# ai_breakout_rn52.net
KiCad netlist of a schematic drawn in EAGLE
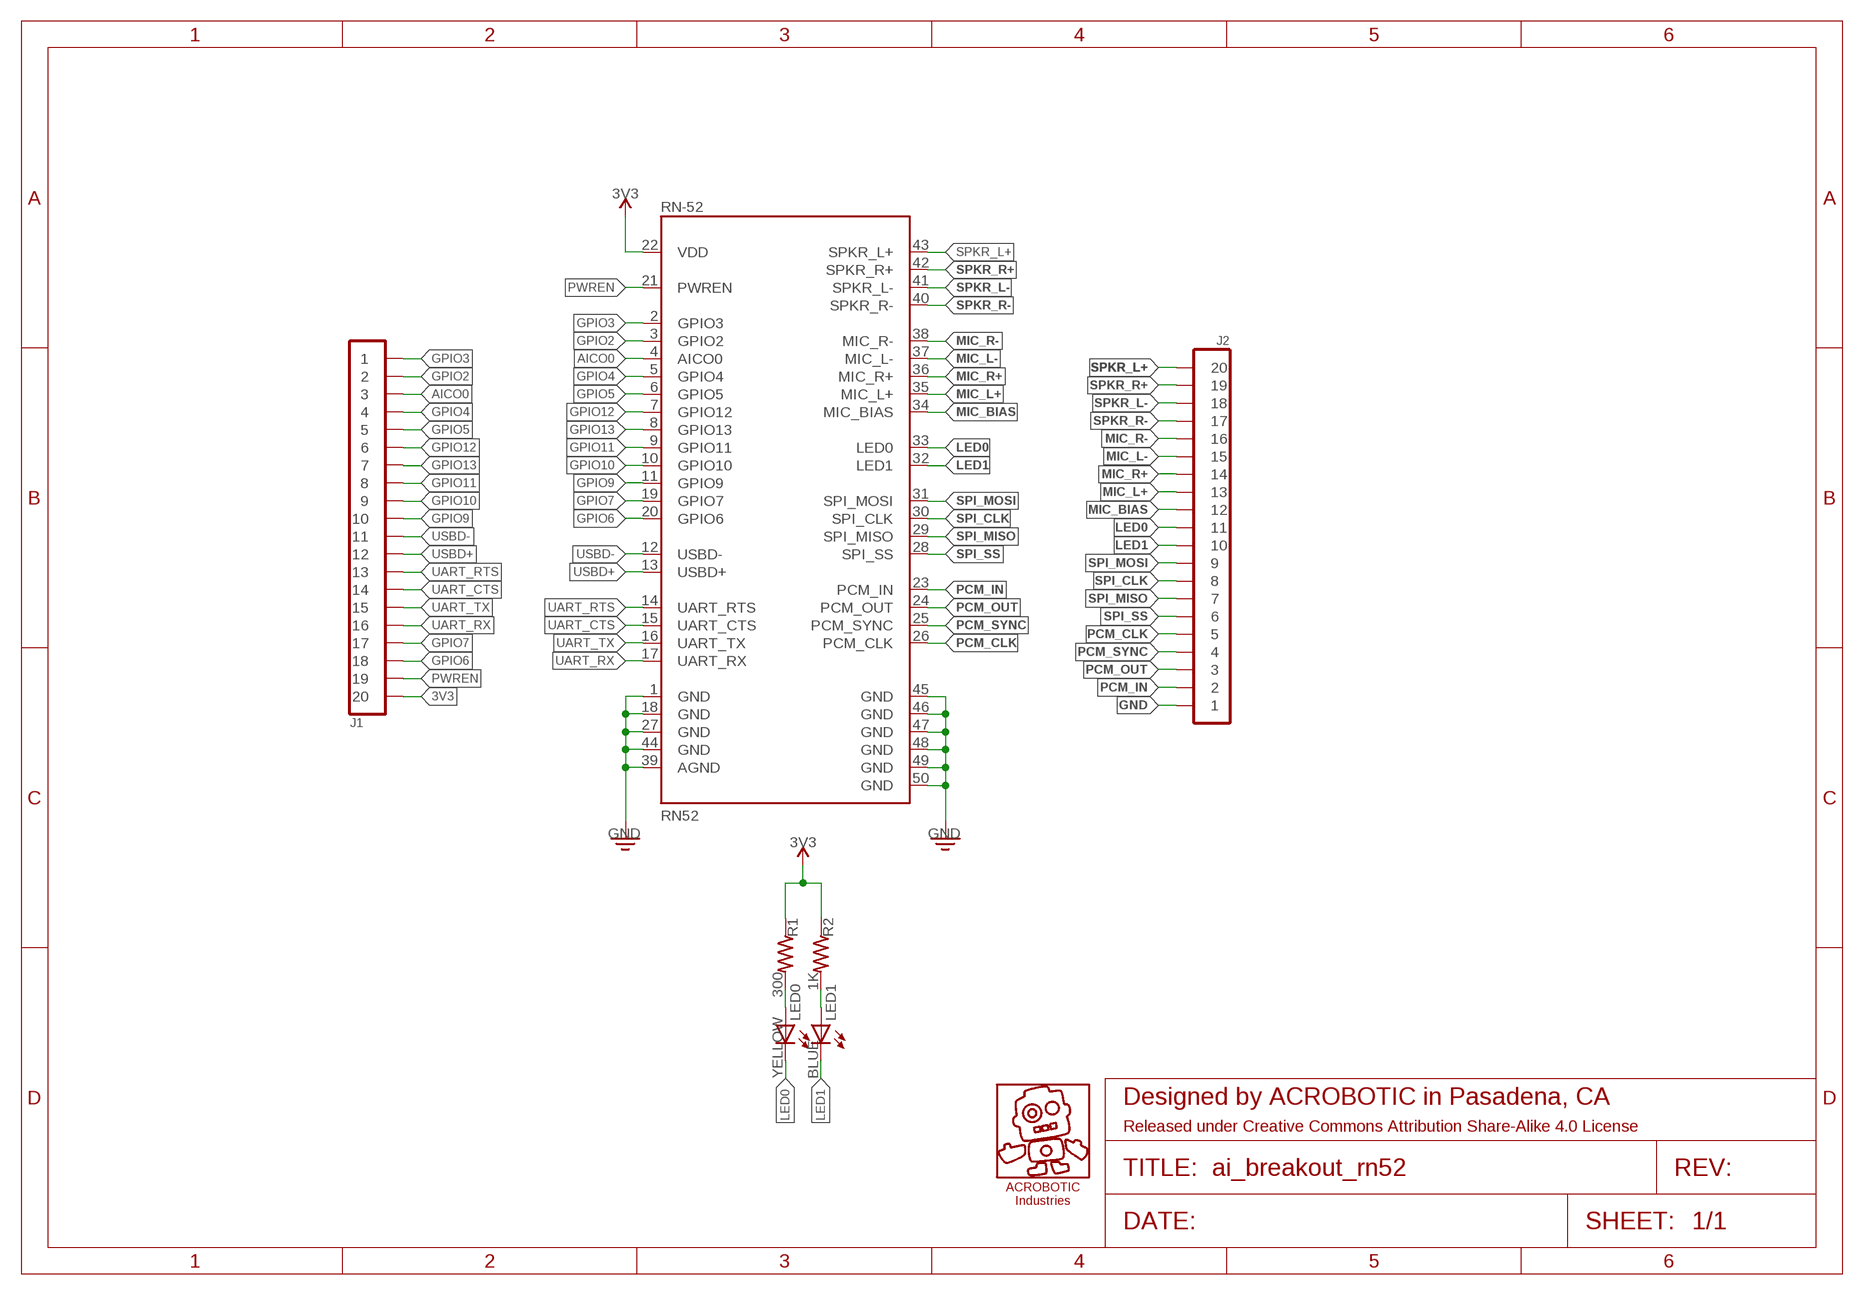
[diagram p0: schematic, sheet 1]

(export (version "E")
  (design (tool "Eeschema 10.0.6"))
  (components
    (comp (ref "FRAME1")
      (value "FRAME-LETTER")
      (footprint "eagle-import:CREATIVE-COMMONS")
      (fields (field (name "REV") "1.1"))
      (libsource (lib "eagle-import") (part "FRAME-LETTER"))
    )
    (comp (ref "J1")
      (value "1X20")
      (footprint "eagle-import:1X20")
      (libsource (lib "eagle-import") (part "1X20"))
    )
    (comp (ref "J2")
      (value "1X20")
      (footprint "eagle-import:1X20")
      (libsource (lib "eagle-import") (part "1X20"))
    )
    (comp (ref "LED0")
      (value "YELLOW")
      (footprint "eagle-import:LED-0603")
      (libsource (lib "eagle-import") (part "LED0603"))
    )
    (comp (ref "LED1")
      (value "BLUE")
      (footprint "eagle-import:LED-0603")
      (libsource (lib "eagle-import") (part "LED0603"))
    )
    (comp (ref "R1")
      (value "300")
      (footprint "eagle-import:RES-0603")
      (libsource (lib "eagle-import") (part "RES0603"))
    )
    (comp (ref "R2")
      (value "1K")
      (footprint "eagle-import:RES-0603")
      (libsource (lib "eagle-import") (part "RES0603"))
    )
    (comp (ref "RN-52")
      (value "RN52")
      (footprint "eagle-import:RN52")
      (libsource (lib "eagle-import") (part "RN52"))
    )
    (comp (ref "U$3")
      (value "AI-LOGOXS")
      (footprint "eagle-import:AI-LOGO-XS")
      (libsource (lib "eagle-import") (part "AI-LOGOXS"))
    )
  )
  (nets
    (net (code "1") (name "3V3") (class "Default")
      (node (ref "J1") (pin "20") (pinfunction "20_20") (pintype "bidirectional"))
      (node (ref "R1") (pin "1") (pinfunction "1_1") (pintype "passive"))
      (node (ref "R2") (pin "1") (pinfunction "1_1") (pintype "passive"))
      (node (ref "RN-52") (pin "22") (pinfunction "VDD_22") (pintype "bidirectional"))
    )
    (net (code "2") (name "AICO0") (class "Default")
      (node (ref "J1") (pin "3") (pinfunction "3_3") (pintype "bidirectional"))
      (node (ref "RN-52") (pin "4") (pinfunction "AICO0_4") (pintype "bidirectional"))
    )
    (net (code "3") (name "GND") (class "Default")
      (node (ref "J2") (pin "1") (pinfunction "1_1") (pintype "bidirectional"))
      (node (ref "RN-52") (pin "1") (pinfunction "GND_1") (pintype "bidirectional"))
      (node (ref "RN-52") (pin "18") (pinfunction "GND_18") (pintype "bidirectional"))
      (node (ref "RN-52") (pin "27") (pinfunction "GND_27") (pintype "bidirectional"))
      (node (ref "RN-52") (pin "39") (pinfunction "AGND_39") (pintype "bidirectional"))
      (node (ref "RN-52") (pin "44") (pinfunction "GND_44") (pintype "bidirectional"))
      (node (ref "RN-52") (pin "45") (pinfunction "GND_45") (pintype "bidirectional"))
      (node (ref "RN-52") (pin "46") (pinfunction "GND_46") (pintype "bidirectional"))
      (node (ref "RN-52") (pin "47") (pinfunction "GND_47") (pintype "bidirectional"))
      (node (ref "RN-52") (pin "48") (pinfunction "GND_48") (pintype "bidirectional"))
      (node (ref "RN-52") (pin "49") (pinfunction "GND_49") (pintype "bidirectional"))
      (node (ref "RN-52") (pin "50") (pinfunction "GND_50") (pintype "bidirectional"))
    )
    (net (code "4") (name "GPIO2") (class "Default")
      (node (ref "J1") (pin "2") (pinfunction "2_2") (pintype "bidirectional"))
      (node (ref "RN-52") (pin "3") (pinfunction "GPIO2_3") (pintype "bidirectional"))
    )
    (net (code "5") (name "GPIO3") (class "Default")
      (node (ref "J1") (pin "1") (pinfunction "1_1") (pintype "bidirectional"))
      (node (ref "RN-52") (pin "2") (pinfunction "GPIO3_2") (pintype "bidirectional"))
    )
    (net (code "6") (name "GPIO4") (class "Default")
      (node (ref "J1") (pin "4") (pinfunction "4_4") (pintype "bidirectional"))
      (node (ref "RN-52") (pin "5") (pinfunction "GPIO4_5") (pintype "bidirectional"))
    )
    (net (code "7") (name "GPIO5") (class "Default")
      (node (ref "J1") (pin "5") (pinfunction "5_5") (pintype "bidirectional"))
      (node (ref "RN-52") (pin "6") (pinfunction "GPIO5_6") (pintype "bidirectional"))
    )
    (net (code "8") (name "GPIO6") (class "Default")
      (node (ref "J1") (pin "18") (pinfunction "18_18") (pintype "bidirectional"))
      (node (ref "RN-52") (pin "20") (pinfunction "GPIO6_20") (pintype "bidirectional"))
    )
    (net (code "9") (name "GPIO7") (class "Default")
      (node (ref "J1") (pin "17") (pinfunction "17_17") (pintype "bidirectional"))
      (node (ref "RN-52") (pin "19") (pinfunction "GPIO7_19") (pintype "bidirectional"))
    )
    (net (code "10") (name "GPIO9") (class "Default")
      (node (ref "J1") (pin "10") (pinfunction "10_10") (pintype "bidirectional"))
      (node (ref "RN-52") (pin "11") (pinfunction "GPIO9_11") (pintype "bidirectional"))
    )
    (net (code "11") (name "GPIO10") (class "Default")
      (node (ref "J1") (pin "9") (pinfunction "9_9") (pintype "bidirectional"))
      (node (ref "RN-52") (pin "10") (pinfunction "GPIO10_10") (pintype "bidirectional"))
    )
    (net (code "12") (name "GPIO11") (class "Default")
      (node (ref "J1") (pin "8") (pinfunction "8_8") (pintype "bidirectional"))
      (node (ref "RN-52") (pin "9") (pinfunction "GPIO11_9") (pintype "bidirectional"))
    )
    (net (code "13") (name "GPIO12") (class "Default")
      (node (ref "J1") (pin "6") (pinfunction "6_6") (pintype "bidirectional"))
      (node (ref "RN-52") (pin "7") (pinfunction "GPIO12_7") (pintype "bidirectional"))
    )
    (net (code "14") (name "GPIO13") (class "Default")
      (node (ref "J1") (pin "7") (pinfunction "7_7") (pintype "bidirectional"))
      (node (ref "RN-52") (pin "8") (pinfunction "GPIO13_8") (pintype "bidirectional"))
    )
    (net (code "15") (name "LED0") (class "Default")
      (node (ref "J2") (pin "11") (pinfunction "11_11") (pintype "bidirectional"))
      (node (ref "LED0") (pin "C") (pinfunction "C_C") (pintype "passive"))
      (node (ref "RN-52") (pin "33") (pinfunction "LED0_33") (pintype "bidirectional"))
    )
    (net (code "16") (name "LED1") (class "Default")
      (node (ref "J2") (pin "10") (pinfunction "10_10") (pintype "bidirectional"))
      (node (ref "LED1") (pin "C") (pinfunction "C_C") (pintype "passive"))
      (node (ref "RN-52") (pin "32") (pinfunction "LED1_32") (pintype "bidirectional"))
    )
    (net (code "17") (name "MIC_BIAS") (class "Default")
      (node (ref "J2") (pin "12") (pinfunction "12_12") (pintype "bidirectional"))
      (node (ref "RN-52") (pin "34") (pinfunction "MIC_BIAS_34") (pintype "bidirectional"))
    )
    (net (code "18") (name "MIC_L+") (class "Default")
      (node (ref "J2") (pin "13") (pinfunction "13_13") (pintype "bidirectional"))
      (node (ref "RN-52") (pin "35") (pinfunction "MIC_L+_35") (pintype "bidirectional"))
    )
    (net (code "19") (name "MIC_L-") (class "Default")
      (node (ref "J2") (pin "15") (pinfunction "15_15") (pintype "bidirectional"))
      (node (ref "RN-52") (pin "37") (pinfunction "MIC_L-_37") (pintype "bidirectional"))
    )
    (net (code "20") (name "MIC_R+") (class "Default")
      (node (ref "J2") (pin "14") (pinfunction "14_14") (pintype "bidirectional"))
      (node (ref "RN-52") (pin "36") (pinfunction "MIC_R+_36") (pintype "bidirectional"))
    )
    (net (code "21") (name "MIC_R-") (class "Default")
      (node (ref "J2") (pin "16") (pinfunction "16_16") (pintype "bidirectional"))
      (node (ref "RN-52") (pin "38") (pinfunction "MIC_R-_38") (pintype "bidirectional"))
    )
    (net (code "22") (name "Net-(LED0-PadA)") (class "Default")
      (node (ref "LED0") (pin "A") (pinfunction "A_A") (pintype "passive"))
      (node (ref "R1") (pin "2") (pinfunction "2_2") (pintype "passive"))
    )
    (net (code "23") (name "Net-(LED1-PadA)") (class "Default")
      (node (ref "LED1") (pin "A") (pinfunction "A_A") (pintype "passive"))
      (node (ref "R2") (pin "2") (pinfunction "2_2") (pintype "passive"))
    )
    (net (code "24") (name "PCM_CLK") (class "Default")
      (node (ref "J2") (pin "5") (pinfunction "5_5") (pintype "bidirectional"))
      (node (ref "RN-52") (pin "26") (pinfunction "PCM_CLK_26") (pintype "bidirectional"))
    )
    (net (code "25") (name "PCM_IN") (class "Default")
      (node (ref "J2") (pin "2") (pinfunction "2_2") (pintype "bidirectional"))
      (node (ref "RN-52") (pin "23") (pinfunction "PCM_IN_23") (pintype "bidirectional"))
    )
    (net (code "26") (name "PCM_OUT") (class "Default")
      (node (ref "J2") (pin "3") (pinfunction "3_3") (pintype "bidirectional"))
      (node (ref "RN-52") (pin "24") (pinfunction "PCM_OUT_24") (pintype "bidirectional"))
    )
    (net (code "27") (name "PCM_SYNC") (class "Default")
      (node (ref "J2") (pin "4") (pinfunction "4_4") (pintype "bidirectional"))
      (node (ref "RN-52") (pin "25") (pinfunction "PCM_SYNC_25") (pintype "bidirectional"))
    )
    (net (code "28") (name "PWREN") (class "Default")
      (node (ref "J1") (pin "19") (pinfunction "19_19") (pintype "bidirectional"))
      (node (ref "RN-52") (pin "21") (pinfunction "PWREN_21") (pintype "bidirectional"))
    )
    (net (code "29") (name "SPI_CLK") (class "Default")
      (node (ref "J2") (pin "8") (pinfunction "8_8") (pintype "bidirectional"))
      (node (ref "RN-52") (pin "30") (pinfunction "SPI_CLK_30") (pintype "bidirectional"))
    )
    (net (code "30") (name "SPI_MISO") (class "Default")
      (node (ref "J2") (pin "7") (pinfunction "7_7") (pintype "bidirectional"))
      (node (ref "RN-52") (pin "29") (pinfunction "SPI_MISO_29") (pintype "bidirectional"))
    )
    (net (code "31") (name "SPI_MOSI") (class "Default")
      (node (ref "J2") (pin "9") (pinfunction "9_9") (pintype "bidirectional"))
      (node (ref "RN-52") (pin "31") (pinfunction "SPI_MOSI_31") (pintype "bidirectional"))
    )
    (net (code "32") (name "SPI_SS") (class "Default")
      (node (ref "J2") (pin "6") (pinfunction "6_6") (pintype "bidirectional"))
      (node (ref "RN-52") (pin "28") (pinfunction "SPI_SS_28") (pintype "bidirectional"))
    )
    (net (code "33") (name "SPKR_L+") (class "Default")
      (node (ref "J2") (pin "20") (pinfunction "20_20") (pintype "bidirectional"))
      (node (ref "RN-52") (pin "43") (pinfunction "SPKR_L+_43") (pintype "bidirectional"))
    )
    (net (code "34") (name "SPKR_L-") (class "Default")
      (node (ref "J2") (pin "18") (pinfunction "18_18") (pintype "bidirectional"))
      (node (ref "RN-52") (pin "41") (pinfunction "SPKR_L-_41") (pintype "bidirectional"))
    )
    (net (code "35") (name "SPKR_R+") (class "Default")
      (node (ref "J2") (pin "19") (pinfunction "19_19") (pintype "bidirectional"))
      (node (ref "RN-52") (pin "42") (pinfunction "SPKR_R+_42") (pintype "bidirectional"))
    )
    (net (code "36") (name "SPKR_R-") (class "Default")
      (node (ref "J2") (pin "17") (pinfunction "17_17") (pintype "bidirectional"))
      (node (ref "RN-52") (pin "40") (pinfunction "SPKR_R-_40") (pintype "bidirectional"))
    )
    (net (code "37") (name "UART_CTS") (class "Default")
      (node (ref "J1") (pin "14") (pinfunction "14_14") (pintype "bidirectional"))
      (node (ref "RN-52") (pin "15") (pinfunction "UART_CTS_15") (pintype "bidirectional"))
    )
    (net (code "38") (name "UART_RTS") (class "Default")
      (node (ref "J1") (pin "13") (pinfunction "13_13") (pintype "bidirectional"))
      (node (ref "RN-52") (pin "14") (pinfunction "UART_RTS_14") (pintype "bidirectional"))
    )
    (net (code "39") (name "UART_RX") (class "Default")
      (node (ref "J1") (pin "16") (pinfunction "16_16") (pintype "bidirectional"))
      (node (ref "RN-52") (pin "17") (pinfunction "UART_RX_17") (pintype "bidirectional"))
    )
    (net (code "40") (name "UART_TX") (class "Default")
      (node (ref "J1") (pin "15") (pinfunction "15_15") (pintype "bidirectional"))
      (node (ref "RN-52") (pin "16") (pinfunction "UART_TX_16") (pintype "bidirectional"))
    )
    (net (code "41") (name "USBD+") (class "Default")
      (node (ref "J1") (pin "12") (pinfunction "12_12") (pintype "bidirectional"))
      (node (ref "RN-52") (pin "13") (pinfunction "USBD+_13") (pintype "bidirectional"))
    )
    (net (code "42") (name "USBD-") (class "Default")
      (node (ref "J1") (pin "11") (pinfunction "11_11") (pintype "bidirectional"))
      (node (ref "RN-52") (pin "12") (pinfunction "USBD-_12") (pintype "bidirectional"))
    )
  )
)
